# PLACA_PROYECTO_FINAL_ELECTRONICA.net
KiCad netlist of a schematic drawn in EAGLE
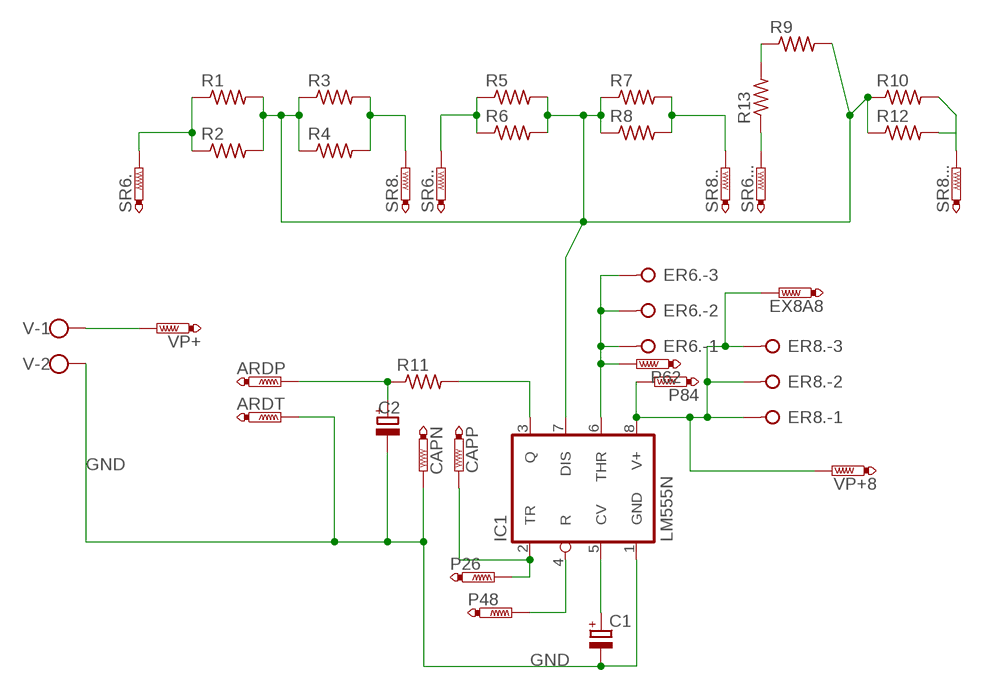
[diagram p0: schematic, sheet 1]

(export (version "E")
  (design (tool "Eeschema 10.0.6"))
  (components
    (comp (ref "ARDP")
      (value "PTR1PAD1-17")
      (footprint "eagle-import:P1-17")
      (libsource (lib "eagle-import") (part "PTR1PAD1-17"))
    )
    (comp (ref "ARDT")
      (value "PTR1PAD1-13")
      (footprint "eagle-import:P1-13")
      (libsource (lib "eagle-import") (part "PTR1PAD1-13"))
    )
    (comp (ref "C1")
      (value "CPOL-EUE2,5-6E")
      (footprint "eagle-import:E2,5-6E")
      (libsource (lib "eagle-import") (part "CPOL-EUE2,5-6E"))
    )
    (comp (ref "C2")
      (value "CPOL-EUE2,5-6E")
      (footprint "eagle-import:E2,5-6E")
      (libsource (lib "eagle-import") (part "CPOL-EUE2,5-6E"))
    )
    (comp (ref "CAPN")
      (value "PTR1PAD1-17")
      (footprint "eagle-import:P1-17")
      (libsource (lib "eagle-import") (part "PTR1PAD1-17"))
    )
    (comp (ref "CAPP")
      (value "PTR1PAD1-17")
      (footprint "eagle-import:P1-17")
      (libsource (lib "eagle-import") (part "PTR1PAD1-17"))
    )
    (comp (ref "ER6.")
      (value "W237-3E")
      (footprint "eagle-import:W237-3E")
      (libsource (lib "eagle-import") (part "W237-3E"))
    )
    (comp (ref "ER8.")
      (value "W237-3E")
      (footprint "eagle-import:W237-3E")
      (libsource (lib "eagle-import") (part "W237-3E"))
    )
    (comp (ref "EX8A8")
      (value "PTR1PAD1-13")
      (footprint "eagle-import:P1-13")
      (libsource (lib "eagle-import") (part "PTR1PAD1-13"))
    )
    (comp (ref "IC1")
      (value "LM555N")
      (footprint "eagle-import:DIL08")
      (libsource (lib "eagle-import") (part "555NLM"))
    )
    (comp (ref "P26")
      (value "PTR1PAD1-17")
      (footprint "eagle-import:P1-17")
      (libsource (lib "eagle-import") (part "PTR1PAD1-17"))
    )
    (comp (ref "P48")
      (value "PTR1PAD1-17")
      (footprint "eagle-import:P1-17")
      (libsource (lib "eagle-import") (part "PTR1PAD1-17"))
    )
    (comp (ref "P62")
      (value "PTR1PAD1-17")
      (footprint "eagle-import:P1-17")
      (libsource (lib "eagle-import") (part "PTR1PAD1-17"))
    )
    (comp (ref "P84")
      (value "PTR1PAD1-17")
      (footprint "eagle-import:P1-17")
      (libsource (lib "eagle-import") (part "PTR1PAD1-17"))
    )
    (comp (ref "R1")
      (value "R-US_0204/7")
      (footprint "eagle-import:0204_7")
      (libsource (lib "eagle-import") (part "R-US_0204/7"))
    )
    (comp (ref "R2")
      (value "R-US_0204/7")
      (footprint "eagle-import:0204_7")
      (libsource (lib "eagle-import") (part "R-US_0204/7"))
    )
    (comp (ref "R3")
      (value "R-US_0204/7")
      (footprint "eagle-import:0204_7")
      (libsource (lib "eagle-import") (part "R-US_0204/7"))
    )
    (comp (ref "R4")
      (value "R-US_0204/7")
      (footprint "eagle-import:0204_7")
      (libsource (lib "eagle-import") (part "R-US_0204/7"))
    )
    (comp (ref "R5")
      (value "R-US_0204/7")
      (footprint "eagle-import:0204_7")
      (libsource (lib "eagle-import") (part "R-US_0204/7"))
    )
    (comp (ref "R6")
      (value "R-US_0204/7")
      (footprint "eagle-import:0204_7")
      (libsource (lib "eagle-import") (part "R-US_0204/7"))
    )
    (comp (ref "R7")
      (value "R-US_0204/7")
      (footprint "eagle-import:0204_7")
      (libsource (lib "eagle-import") (part "R-US_0204/7"))
    )
    (comp (ref "R8")
      (value "R-US_0204/7")
      (footprint "eagle-import:0204_7")
      (libsource (lib "eagle-import") (part "R-US_0204/7"))
    )
    (comp (ref "R9")
      (value "R-US_0204/7")
      (footprint "eagle-import:0204_7")
      (libsource (lib "eagle-import") (part "R-US_0204/7"))
    )
    (comp (ref "R10")
      (value "R-US_0204/7")
      (footprint "eagle-import:0204_7")
      (libsource (lib "eagle-import") (part "R-US_0204/7"))
    )
    (comp (ref "R11")
      (value "R-US_0204/7")
      (footprint "eagle-import:0204_7")
      (libsource (lib "eagle-import") (part "R-US_0204/7"))
    )
    (comp (ref "R12")
      (value "R-US_0204/7")
      (footprint "eagle-import:0204_7")
      (libsource (lib "eagle-import") (part "R-US_0204/7"))
    )
    (comp (ref "R13")
      (value "R-US_0204/7")
      (footprint "eagle-import:0204_7")
      (libsource (lib "eagle-import") (part "R-US_0204/7"))
    )
    (comp (ref "SR6.")
      (value "PTR1PAD1-13")
      (footprint "eagle-import:P1-13")
      (libsource (lib "eagle-import") (part "PTR1PAD1-13"))
    )
    (comp (ref "SR6..")
      (value "PTR1PAD1-13")
      (footprint "eagle-import:P1-13")
      (libsource (lib "eagle-import") (part "PTR1PAD1-13"))
    )
    (comp (ref "SR6...")
      (value "PTR1PAD1-13")
      (footprint "eagle-import:P1-13")
      (libsource (lib "eagle-import") (part "PTR1PAD1-13"))
    )
    (comp (ref "SR8.")
      (value "PTR1PAD1-13")
      (footprint "eagle-import:P1-13")
      (libsource (lib "eagle-import") (part "PTR1PAD1-13"))
    )
    (comp (ref "SR8..")
      (value "PTR1PAD1-13")
      (footprint "eagle-import:P1-13")
      (libsource (lib "eagle-import") (part "PTR1PAD1-13"))
    )
    (comp (ref "SR8...")
      (value "PTR1PAD1-13")
      (footprint "eagle-import:P1-13")
      (libsource (lib "eagle-import") (part "PTR1PAD1-13"))
    )
    (comp (ref "V")
      (value "W237-102")
      (footprint "eagle-import:W237-102")
      (fields (field (name "MPN") "237-102"))
      (libsource (lib "eagle-import") (part "W237-102"))
    )
    (comp (ref "VP+")
      (value "PTR1PAD1-13")
      (footprint "eagle-import:P1-13")
      (libsource (lib "eagle-import") (part "PTR1PAD1-13"))
    )
    (comp (ref "VP+8")
      (value "PTR1PAD1-13")
      (footprint "eagle-import:P1-13")
      (libsource (lib "eagle-import") (part "PTR1PAD1-13"))
    )
  )
  (nets
    (net (code "1") (name "/GND") (class "Default")
      (node (ref "ARDT") (pin "TP") (pinfunction "TP_TP") (pintype "input"))
      (node (ref "C1") (pin "-") (pinfunction "-_-") (pintype "passive"))
      (node (ref "C2") (pin "-") (pinfunction "-_-") (pintype "passive"))
      (node (ref "CAPN") (pin "TP") (pinfunction "TP_TP") (pintype "input"))
      (node (ref "IC1") (pin "1") (pinfunction "GND_1") (pintype "power_in"))
      (node (ref "V") (pin "2") (pinfunction "KL_2") (pintype "passive"))
    )
    (net (code "2") (name "Net-(ARDP-PadTP)") (class "Default")
      (node (ref "ARDP") (pin "TP") (pinfunction "TP_TP") (pintype "input"))
      (node (ref "C2") (pin "+") (pinfunction "+_+") (pintype "passive"))
      (node (ref "R11") (pin "1") (pinfunction "1_1") (pintype "passive"))
    )
    (net (code "3") (name "Net-(ER6.A-KL)") (class "Default")
      (node (ref "ER6.") (pin "1") (pinfunction "KL_1") (pintype "passive"))
      (node (ref "ER6.") (pin "2") (pinfunction "KL_2") (pintype "passive"))
      (node (ref "ER6.") (pin "3") (pinfunction "KL_3") (pintype "passive"))
      (node (ref "IC1") (pin "6") (pinfunction "THR_6") (pintype "input"))
      (node (ref "P62") (pin "TP") (pinfunction "TP_TP") (pintype "input"))
    )
    (net (code "4") (name "Net-(ER8.A-KL)") (class "Default")
      (node (ref "ER8.") (pin "1") (pinfunction "KL_1") (pintype "passive"))
      (node (ref "ER8.") (pin "2") (pinfunction "KL_2") (pintype "passive"))
      (node (ref "ER8.") (pin "3") (pinfunction "KL_3") (pintype "passive"))
      (node (ref "EX8A8") (pin "TP") (pinfunction "TP_TP") (pintype "input"))
      (node (ref "IC1") (pin "8") (pinfunction "V+_8") (pintype "power_in"))
      (node (ref "P84") (pin "TP") (pinfunction "TP_TP") (pintype "input"))
      (node (ref "VP+8") (pin "TP") (pinfunction "TP_TP") (pintype "input"))
    )
    (net (code "5") (name "Net-(IC1-CV)") (class "Default")
      (node (ref "C1") (pin "+") (pinfunction "+_+") (pintype "passive"))
      (node (ref "IC1") (pin "5") (pinfunction "CV_5") (pintype "input"))
    )
    (net (code "6") (name "Net-(IC1-DIS)") (class "Default")
      (node (ref "IC1") (pin "7") (pinfunction "DIS_7") (pintype "input"))
      (node (ref "R1") (pin "2") (pinfunction "2_2") (pintype "passive"))
      (node (ref "R10") (pin "1") (pinfunction "1_1") (pintype "passive"))
      (node (ref "R12") (pin "1") (pinfunction "1_1") (pintype "passive"))
      (node (ref "R2") (pin "2") (pinfunction "2_2") (pintype "passive"))
      (node (ref "R3") (pin "1") (pinfunction "1_1") (pintype "passive"))
      (node (ref "R4") (pin "1") (pinfunction "1_1") (pintype "passive"))
      (node (ref "R5") (pin "2") (pinfunction "2_2") (pintype "passive"))
      (node (ref "R6") (pin "2") (pinfunction "2_2") (pintype "passive"))
      (node (ref "R7") (pin "1") (pinfunction "1_1") (pintype "passive"))
      (node (ref "R8") (pin "1") (pinfunction "1_1") (pintype "passive"))
      (node (ref "R9") (pin "2") (pinfunction "2_2") (pintype "passive"))
    )
    (net (code "7") (name "Net-(IC1-Q)") (class "Default")
      (node (ref "IC1") (pin "3") (pinfunction "Q_3") (pintype "output"))
      (node (ref "R11") (pin "2") (pinfunction "2_2") (pintype "passive"))
    )
    (net (code "8") (name "Net-(IC1-R)") (class "Default")
      (node (ref "IC1") (pin "4") (pinfunction "R_4") (pintype "input"))
      (node (ref "P48") (pin "TP") (pinfunction "TP_TP") (pintype "input"))
    )
    (net (code "9") (name "Net-(IC1-TR)") (class "Default")
      (node (ref "CAPP") (pin "TP") (pinfunction "TP_TP") (pintype "input"))
      (node (ref "IC1") (pin "2") (pinfunction "TR_2") (pintype "input"))
      (node (ref "P26") (pin "TP") (pinfunction "TP_TP") (pintype "input"))
    )
    (net (code "10") (name "Net-(R1-Pad1)") (class "Default")
      (node (ref "R1") (pin "1") (pinfunction "1_1") (pintype "passive"))
      (node (ref "R2") (pin "1") (pinfunction "1_1") (pintype "passive"))
      (node (ref "SR6.") (pin "TP") (pinfunction "TP_TP") (pintype "input"))
    )
    (net (code "11") (name "Net-(R3-Pad2)") (class "Default")
      (node (ref "R3") (pin "2") (pinfunction "2_2") (pintype "passive"))
      (node (ref "R4") (pin "2") (pinfunction "2_2") (pintype "passive"))
      (node (ref "SR8.") (pin "TP") (pinfunction "TP_TP") (pintype "input"))
    )
    (net (code "12") (name "Net-(R5-Pad1)") (class "Default")
      (node (ref "R5") (pin "1") (pinfunction "1_1") (pintype "passive"))
      (node (ref "R6") (pin "1") (pinfunction "1_1") (pintype "passive"))
      (node (ref "SR6..") (pin "TP") (pinfunction "TP_TP") (pintype "input"))
    )
    (net (code "13") (name "Net-(R7-Pad2)") (class "Default")
      (node (ref "R7") (pin "2") (pinfunction "2_2") (pintype "passive"))
      (node (ref "R8") (pin "2") (pinfunction "2_2") (pintype "passive"))
      (node (ref "SR8..") (pin "TP") (pinfunction "TP_TP") (pintype "input"))
    )
    (net (code "14") (name "Net-(R10-Pad2)") (class "Default")
      (node (ref "R10") (pin "2") (pinfunction "2_2") (pintype "passive"))
      (node (ref "R12") (pin "2") (pinfunction "2_2") (pintype "passive"))
      (node (ref "SR8...") (pin "TP") (pinfunction "TP_TP") (pintype "input"))
    )
    (net (code "15") (name "Net-(R13-Pad1)") (class "Default")
      (node (ref "R13") (pin "1") (pinfunction "1_1") (pintype "passive"))
      (node (ref "SR6...") (pin "TP") (pinfunction "TP_TP") (pintype "input"))
    )
    (net (code "16") (name "Net-(R13-Pad2)") (class "Default")
      (node (ref "R13") (pin "2") (pinfunction "2_2") (pintype "passive"))
      (node (ref "R9") (pin "1") (pinfunction "1_1") (pintype "passive"))
    )
    (net (code "17") (name "Net-(VA-KL)") (class "Default")
      (node (ref "V") (pin "1") (pinfunction "KL_1") (pintype "passive"))
      (node (ref "VP+") (pin "TP") (pinfunction "TP_TP") (pintype "input"))
    )
  )
)
